# Gochermann_Solar_PanelRev3_5.net
KiCad netlist of a schematic drawn in Altium Designer
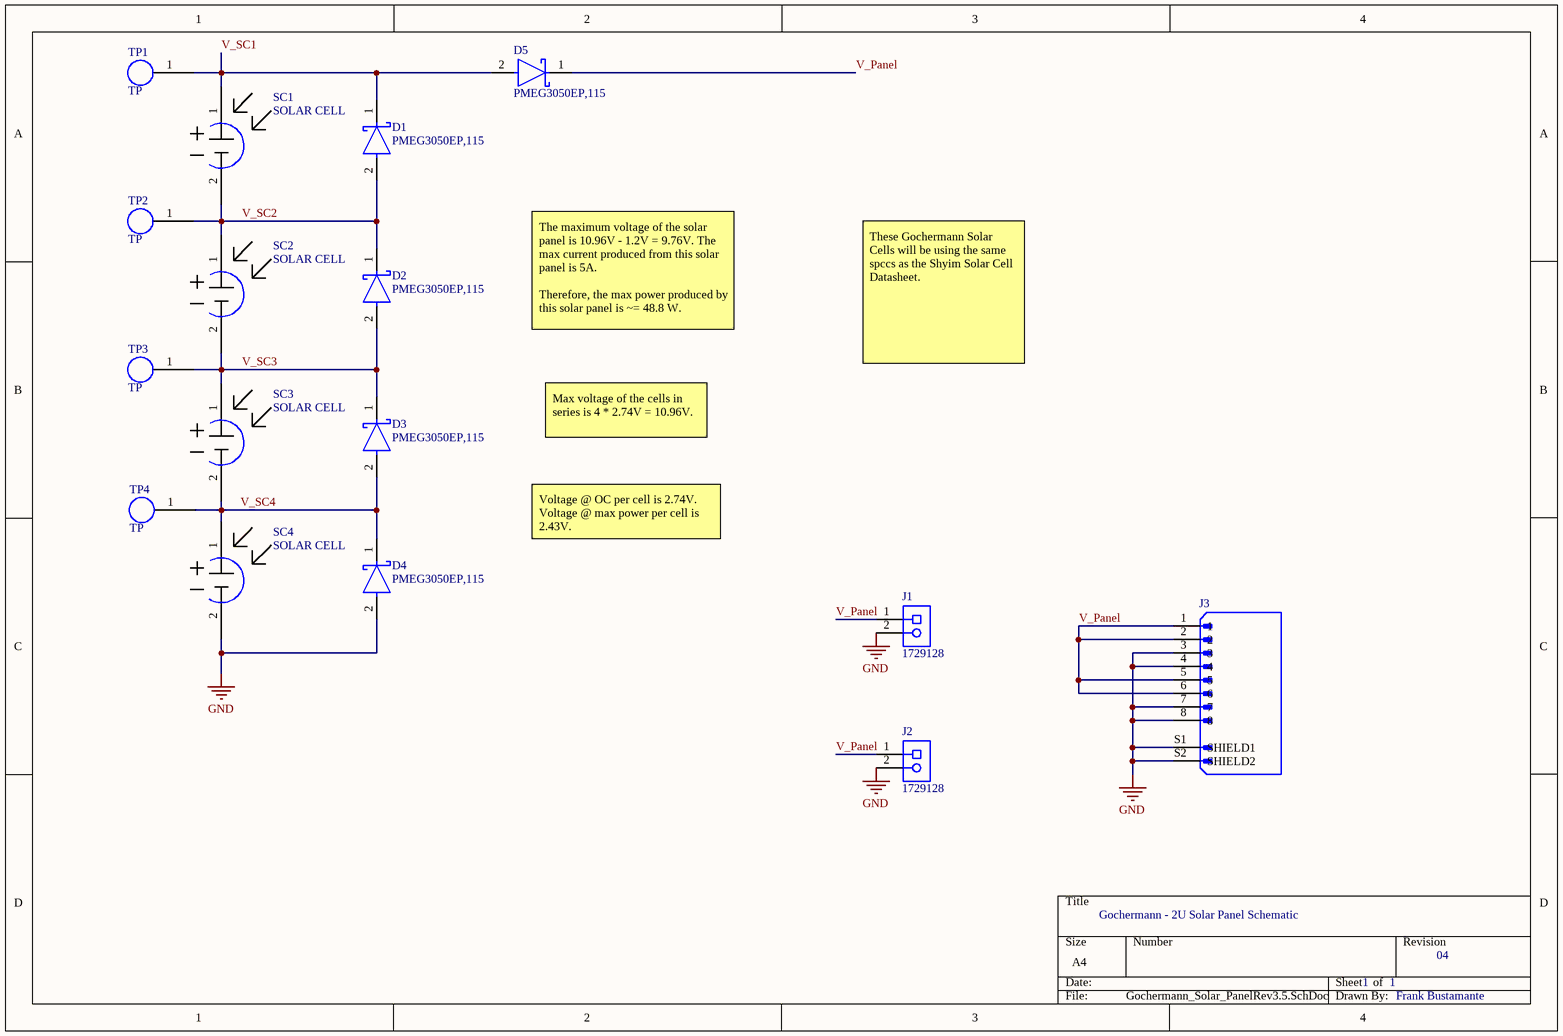
[diagram p0: Gochermann_Solar_PanelRev3.5.SchDoc]

(export (version "E")
  (design (tool "Eeschema 10.0.6"))
  (components
    (comp (ref "D1")
      (value "PMEG3050EP,115")
      (footprint "FP-SOD128-MFG")
      (description "DIODE SCHOTTKY 30V 5A SOD128")
      (libsource (lib "Altium Content Vault") (part "1d6ec82d83fb6aee721767c19dac4b9"))
    )
    (comp (ref "D2")
      (value "PMEG3050EP,115")
      (footprint "FP-SOD128-MFG")
      (description "DIODE SCHOTTKY 30V 5A SOD128")
      (libsource (lib "Altium Content Vault") (part "1d6ec82d83fb6aee721767c19dac4b9"))
    )
    (comp (ref "D3")
      (value "PMEG3050EP,115")
      (footprint "FP-SOD128-MFG")
      (description "DIODE SCHOTTKY 30V 5A SOD128")
      (libsource (lib "Altium Content Vault") (part "1d6ec82d83fb6aee721767c19dac4b9"))
    )
    (comp (ref "D4")
      (value "PMEG3050EP,115")
      (footprint "FP-SOD128-MFG")
      (description "DIODE SCHOTTKY 30V 5A SOD128")
      (libsource (lib "Altium Content Vault") (part "1d6ec82d83fb6aee721767c19dac4b9"))
    )
    (comp (ref "D5")
      (value "PMEG3050EP,115")
      (footprint "FP-SOD128-MFG")
      (description "DIODE SCHOTTKY 30V 5A SOD128")
      (libsource (lib "Altium Content Vault") (part "1d6ec82d83fb6aee721767c19dac4b9"))
    )
    (comp (ref "J1")
      (value "1729128")
      (footprint "PHOE-1729128-2_V")
      (description "PCB Terminal Block, 13.5 A, 400 V, 2-Pin THD, RoHS, Bulk")
      (fields
        (field (name "MANUFACTURER") "Phoenix Contact")
        (field (name "SAFETY APPROVAL") "CSA,CUL,CB,EAC")
      )
      (libsource (lib "Altium Content Vault") (part "CN-2P-F-R2"))
    )
    (comp (ref "J2")
      (value "1729128")
      (footprint "PHOE-1729128-2_V")
      (description "PCB Terminal Block, 13.5 A, 400 V, 2-Pin THD, RoHS, Bulk")
      (fields
        (field (name "MANUFACTURER") "Phoenix Contact")
        (field (name "SAFETY APPROVAL") "CSA,CUL,CB,EAC")
      )
      (libsource (lib "Altium Content Vault") (part "CN-2P-F-R2"))
    )
    (comp (ref "J3")
      (value "~")
      (footprint "MOLEX_5040500891")
      (libsource (lib "Schlib5.0") (part "EPS_5040500891_Molex_Connector"))
    )
    (comp (ref "SC1")
      (value "SOLAR CELL")
      (footprint "SOL_CEL_GOCHERMANN")
      (description "Solar Cell from Gochermann")
      (fields (field (name "INTERNALPART#") "SC-3GA-3"))
      (libsource (lib "Schlib5.0") (part "SOL_CEL_Gochermann"))
    )
    (comp (ref "SC2")
      (value "SOLAR CELL")
      (footprint "SOL_CEL_GOCHERMANN")
      (description "Solar Cell from Gochermann")
      (fields (field (name "INTERNALPART#") "SC-3GA-3"))
      (libsource (lib "Schlib5.0") (part "SOL_CEL_Gochermann"))
    )
    (comp (ref "SC3")
      (value "SOLAR CELL")
      (footprint "SOL_CEL_GOCHERMANN")
      (description "Solar Cell from Gochermann")
      (fields (field (name "INTERNALPART#") "SC-3GA-3"))
      (libsource (lib "Schlib5.0") (part "SOL_CEL_Gochermann"))
    )
    (comp (ref "SC4")
      (value "SOLAR CELL")
      (footprint "SOL_CEL_GOCHERMANN")
      (description "Solar Cell from Gochermann")
      (fields (field (name "INTERNALPART#") "SC-3GA-3"))
      (libsource (lib "Schlib5.0") (part "SOL_CEL_Gochermann"))
    )
    (comp (ref "TP1") (value "TP") (footprint "TP") (libsource (lib "Schlib3") (part "TP")))
    (comp (ref "TP2") (value "TP") (footprint "TP") (libsource (lib "Schlib3") (part "TP")))
    (comp (ref "TP3") (value "TP") (footprint "TP") (libsource (lib "Schlib3") (part "TP")))
    (comp (ref "TP4") (value "TP") (footprint "TP") (libsource (lib "Schlib3") (part "TP")))
  )
  (nets
    (net (code "1") (name "/V_Panel") (class "Default")
      (node (ref "D5") (pin "1") (pinfunction "C_1") (pintype "passive"))
      (node (ref "J1") (pin "1") (pinfunction "1_1") (pintype "passive"))
      (node (ref "J2") (pin "1") (pinfunction "1_1") (pintype "passive"))
      (node (ref "J3") (pin "1") (pinfunction "1_1") (pintype "passive"))
      (node (ref "J3") (pin "2") (pinfunction "2_2") (pintype "passive"))
      (node (ref "J3") (pin "5") (pinfunction "5_5") (pintype "passive"))
      (node (ref "J3") (pin "6") (pinfunction "6_6") (pintype "passive"))
    )
    (net (code "2") (name "/V_SC1") (class "Default")
      (node (ref "D1") (pin "1") (pinfunction "C_1") (pintype "passive"))
      (node (ref "D5") (pin "2") (pinfunction "A_2") (pintype "passive"))
      (node (ref "SC1") (pin "1") (pinfunction "1_1") (pintype "passive"))
      (node (ref "TP1") (pin "1") (pinfunction "1_1") (pintype "passive"))
    )
    (net (code "3") (name "/V_SC2") (class "Default")
      (node (ref "D1") (pin "2") (pinfunction "A_2") (pintype "passive"))
      (node (ref "D2") (pin "1") (pinfunction "C_1") (pintype "passive"))
      (node (ref "SC1") (pin "2") (pinfunction "2_2") (pintype "passive"))
      (node (ref "SC2") (pin "1") (pinfunction "1_1") (pintype "passive"))
      (node (ref "TP2") (pin "1") (pinfunction "1_1") (pintype "passive"))
    )
    (net (code "4") (name "/V_SC3") (class "Default")
      (node (ref "D2") (pin "2") (pinfunction "A_2") (pintype "passive"))
      (node (ref "D3") (pin "1") (pinfunction "C_1") (pintype "passive"))
      (node (ref "SC2") (pin "2") (pinfunction "2_2") (pintype "passive"))
      (node (ref "SC3") (pin "1") (pinfunction "1_1") (pintype "passive"))
      (node (ref "TP3") (pin "1") (pinfunction "1_1") (pintype "passive"))
    )
    (net (code "5") (name "/V_SC4") (class "Default")
      (node (ref "D3") (pin "2") (pinfunction "A_2") (pintype "passive"))
      (node (ref "D4") (pin "1") (pinfunction "C_1") (pintype "passive"))
      (node (ref "SC3") (pin "2") (pinfunction "2_2") (pintype "passive"))
      (node (ref "SC4") (pin "1") (pinfunction "1_1") (pintype "passive"))
      (node (ref "TP4") (pin "1") (pinfunction "1_1") (pintype "passive"))
    )
    (net (code "6") (name "GND") (class "Default")
      (node (ref "D4") (pin "2") (pinfunction "A_2") (pintype "passive"))
      (node (ref "J1") (pin "2") (pinfunction "2_2") (pintype "passive"))
      (node (ref "J2") (pin "2") (pinfunction "2_2") (pintype "passive"))
      (node (ref "J3") (pin "3") (pinfunction "3_3") (pintype "passive"))
      (node (ref "J3") (pin "4") (pinfunction "4_4") (pintype "passive"))
      (node (ref "J3") (pin "7") (pinfunction "7_7") (pintype "passive"))
      (node (ref "J3") (pin "8") (pinfunction "8_8") (pintype "passive"))
      (node (ref "J3") (pin "S1") (pinfunction "SHIELD1_S1") (pintype "passive"))
      (node (ref "J3") (pin "S2") (pinfunction "SHIELD2_S2") (pintype "passive"))
      (node (ref "SC4") (pin "2") (pinfunction "2_2") (pintype "passive"))
    )
  )
)
